# DAC_Output.net
KiCad netlist of a schematic drawn in Altium Designer
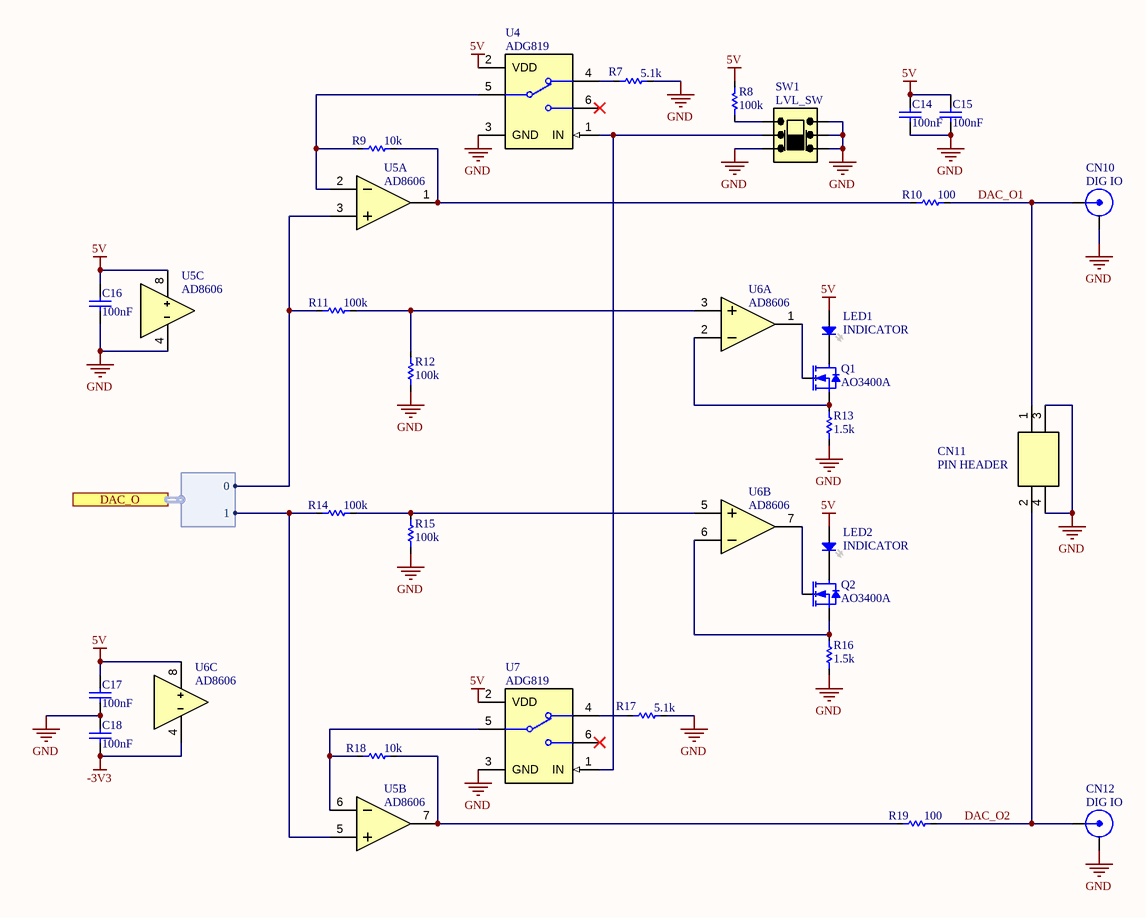
[diagram p0: DAC Output.SchDoc]

(export (version "E")
  (design (tool "Eeschema 10.0.6"))
  (components
    (comp (ref "C14")
      (value "100nF")
      (footprint "CAP_CHIP_0603")
      (description "0603 Multilayer Ceramic Capacitors MLCC")
      (fields (field (name "TOLERANCE") "10%") (field (name "PARTNUMBER") "CC0603KRX7R9BB104"))
      (libsource (lib "Sainsbury Wellcome Centre") (part "Cap"))
    )
    (comp (ref "C15")
      (value "100nF")
      (footprint "CAP_CHIP_0603")
      (description "0603 Multilayer Ceramic Capacitors MLCC")
      (fields (field (name "TOLERANCE") "10%") (field (name "PARTNUMBER") "CC0603KRX7R9BB104"))
      (libsource (lib "Sainsbury Wellcome Centre") (part "Cap"))
    )
    (comp (ref "C16")
      (value "100nF")
      (footprint "CAP_CHIP_0603")
      (description "0603 Multilayer Ceramic Capacitors MLCC")
      (fields (field (name "TOLERANCE") "10%") (field (name "PARTNUMBER") "CC0603KRX7R9BB104"))
      (libsource (lib "Sainsbury Wellcome Centre") (part "Cap"))
    )
    (comp (ref "C17")
      (value "100nF")
      (footprint "CAP_CHIP_0603")
      (description "0603 Multilayer Ceramic Capacitors MLCC")
      (fields (field (name "TOLERANCE") "10%") (field (name "PARTNUMBER") "CC0603KRX7R9BB104"))
      (libsource (lib "Sainsbury Wellcome Centre") (part "Cap"))
    )
    (comp (ref "C18")
      (value "100nF")
      (footprint "CAP_CHIP_0603")
      (description "0603 Multilayer Ceramic Capacitors MLCC")
      (fields (field (name "TOLERANCE") "10%") (field (name "PARTNUMBER") "CC0603KRX7R9BB104"))
      (libsource (lib "Sainsbury Wellcome Centre") (part "Cap"))
    )
    (comp (ref "CN10")
      (value "DIG IO")
      (footprint "BNC-AMP-112515")
      (description "RF BNC Connector, Female, Board Mount, Solder Terminal, Jack")
      (fields (field (name "PARTNUMBER") "112515"))
      (libsource (lib "Sainsbury Wellcome Centre") (part "RF-Jack"))
    )
    (comp (ref "CN11")
      (value "PIN HEADER")
      (footprint "PIN_2.54_2X2P")
      (fields (field (name "PARTNUMBER") "PZ254V-12-4P"))
      (libsource (lib "Sainsbury Wellcome Centre") (part "Header_2X2P"))
    )
    (comp (ref "CN12")
      (value "DIG IO")
      (footprint "BNC-AMP-112515")
      (description "RF BNC Connector, Female, Board Mount, Solder Terminal, Jack")
      (fields (field (name "PARTNUMBER") "112515"))
      (libsource (lib "Sainsbury Wellcome Centre") (part "RF-Jack"))
    )
    (comp (ref "LED1")
      (value "INDICATOR")
      (footprint "LED_CHIP_0805")
      (description "White 0805 Light Emitting Diodes (LED) ROHS")
      (fields (field (name "PARTNUMBER") "KT-0805W"))
      (libsource (lib "Sainsbury Wellcome Centre") (part "LED-WHITE"))
    )
    (comp (ref "LED2")
      (value "INDICATOR")
      (footprint "LED_CHIP_0805")
      (description "White 0805 Light Emitting Diodes (LED) ROHS")
      (fields (field (name "PARTNUMBER") "KT-0805W"))
      (libsource (lib "Sainsbury Wellcome Centre") (part "LED-WHITE"))
    )
    (comp (ref "Q1")
      (value "AO3400A")
      (footprint "SOT23")
      (description "30V 5.7A 26.5mΩ@10V,5.7A 1.4W 1.5V@250uA 1 NChannel SOT-23-3L MOSFETs")
      (fields (field (name "PARTNUMBER") "AO3400A"))
      (libsource (lib "Sainsbury Wellcome Centre") (part "NMOS"))
    )
    (comp (ref "Q2")
      (value "AO3400A")
      (footprint "SOT23")
      (description "30V 5.7A 26.5mΩ@10V,5.7A 1.4W 1.5V@250uA 1 NChannel SOT-23-3L MOSFETs")
      (fields (field (name "PARTNUMBER") "AO3400A"))
      (libsource (lib "Sainsbury Wellcome Centre") (part "NMOS"))
    )
    (comp (ref "R7")
      (value "5.1k")
      (footprint "RES_CHIP_0603")
      (description "100mW Thick Film Resistors 75V ±100ppm/℃ ±1% 0603 Chip Resistor")
      (fields (field (name "TOLERANCE") "1%") (field (name "PARTNUMBER") "0603WAF5101T5E"))
      (libsource (lib "Sainsbury Wellcome Centre") (part "Res"))
    )
    (comp (ref "R8")
      (value "100k")
      (footprint "RES_CHIP_0603")
      (description "100mW Thick Film Resistors 75V ±100ppm/℃ ±1% 0603 Chip Resistor")
      (fields (field (name "PARTNUMBER") "0603WAF1003T5E") (field (name "TOLERANCE") "1%"))
      (libsource (lib "Sainsbury Wellcome Centre") (part "Res"))
    )
    (comp (ref "R9")
      (value "10k")
      (footprint "RES_CHIP_0603")
      (description "100mW Thick Film Resistors 75V ±100ppm/℃ ±1% 0603 Chip Resistor")
      (fields (field (name "PARTNUMBER") "0603WAF1002T5E") (field (name "TOLERANCE") "1%"))
      (libsource (lib "Sainsbury Wellcome Centre") (part "Res"))
    )
    (comp (ref "R10")
      (value "100")
      (footprint "RES_CHIP_0603")
      (description "100mW Thick Film Resistors 75V ±100ppm/℃ ±1% 0603 Chip Resistor")
      (fields (field (name "PARTNUMBER") "0603WAF1000T5E") (field (name "TOLERANCE") "1%"))
      (libsource (lib "Sainsbury Wellcome Centre") (part "Res"))
    )
    (comp (ref "R11")
      (value "100k")
      (footprint "RES_CHIP_0603")
      (description "100mW Thick Film Resistors 75V ±100ppm/℃ ±1% 0603 Chip Resistor")
      (fields (field (name "PARTNUMBER") "0603WAF1003T5E") (field (name "TOLERANCE") "1%"))
      (libsource (lib "Sainsbury Wellcome Centre") (part "Res"))
    )
    (comp (ref "R12")
      (value "100k")
      (footprint "RES_CHIP_0603")
      (description "100mW Thick Film Resistors 75V ±100ppm/℃ ±1% 0603 Chip Resistor")
      (fields (field (name "PARTNUMBER") "0603WAF1003T5E") (field (name "TOLERANCE") "1%"))
      (libsource (lib "Sainsbury Wellcome Centre") (part "Res"))
    )
    (comp (ref "R13")
      (value "1.5k")
      (footprint "RES_CHIP_0603")
      (description "100mW Thick Film Resistors 75V ±100ppm/℃ ±1% 0603 Chip Resistor")
      (fields (field (name "TOLERANCE") "1%") (field (name "PARTNUMBER") "0603WAF1501T5E"))
      (libsource (lib "Sainsbury Wellcome Centre") (part "Res"))
    )
    (comp (ref "R14")
      (value "100k")
      (footprint "RES_CHIP_0603")
      (description "100mW Thick Film Resistors 75V ±100ppm/℃ ±1% 0603 Chip Resistor")
      (fields (field (name "PARTNUMBER") "0603WAF1003T5E") (field (name "TOLERANCE") "1%"))
      (libsource (lib "Sainsbury Wellcome Centre") (part "Res"))
    )
    (comp (ref "R15")
      (value "100k")
      (footprint "RES_CHIP_0603")
      (description "100mW Thick Film Resistors 75V ±100ppm/℃ ±1% 0603 Chip Resistor")
      (fields (field (name "PARTNUMBER") "0603WAF1003T5E") (field (name "TOLERANCE") "1%"))
      (libsource (lib "Sainsbury Wellcome Centre") (part "Res"))
    )
    (comp (ref "R16")
      (value "1.5k")
      (footprint "RES_CHIP_0603")
      (description "100mW Thick Film Resistors 75V ±100ppm/℃ ±1% 0603 Chip Resistor")
      (fields (field (name "TOLERANCE") "1%") (field (name "PARTNUMBER") "0603WAF1501T5E"))
      (libsource (lib "Sainsbury Wellcome Centre") (part "Res"))
    )
    (comp (ref "R17")
      (value "5.1k")
      (footprint "RES_CHIP_0603")
      (description "100mW Thick Film Resistors 75V ±100ppm/℃ ±1% 0603 Chip Resistor")
      (fields (field (name "TOLERANCE") "1%") (field (name "PARTNUMBER") "0603WAF5101T5E"))
      (libsource (lib "Sainsbury Wellcome Centre") (part "Res"))
    )
    (comp (ref "R18")
      (value "10k")
      (footprint "RES_CHIP_0603")
      (description "100mW Thick Film Resistors 75V ±100ppm/℃ ±1% 0603 Chip Resistor")
      (fields (field (name "PARTNUMBER") "0603WAF1002T5E") (field (name "TOLERANCE") "1%"))
      (libsource (lib "Sainsbury Wellcome Centre") (part "Res"))
    )
    (comp (ref "R19")
      (value "100")
      (footprint "RES_CHIP_0603")
      (description "100mW Thick Film Resistors 75V ±100ppm/℃ ±1% 0603 Chip Resistor")
      (fields (field (name "PARTNUMBER") "0603WAF1000T5E") (field (name "TOLERANCE") "1%"))
      (libsource (lib "Sainsbury Wellcome Centre") (part "Res"))
    )
    (comp (ref "SW1")
      (value "LVL_SW")
      (footprint "SW_SLIDE_OS202013MT8")
      (description "Switch Slide ON ON DPDT Top Slide 0.3A 30VDC 10000Cycles PC Pins Thru-Hole Bulk")
      (fields (field (name "PARTNUMBER") "OS202013MT8QN1"))
      (libsource (lib "Sainsbury Wellcome Centre") (part "SLIDE_DPDT"))
    )
    (comp (ref "U4")
      (value "ADG819")
      (footprint "SOT23-6")
      (description "Analog Switch/Analog Multiplexer Single 2: 1 Automotive 6-Pin SOT-23 T/R")
      (fields (field (name "PARTNUMBER") "ADG819BRTZ-REEL7"))
      (libsource (lib "Sainsbury Wellcome Centre") (part "ADG819"))
    )
    (comp (ref "U5")
      (value "AD8606")
      (footprint "VSSOP8_3X3_0.65E")
      (description "Operational Amplifier, 2 Func, 750uV Offset-Max, CMOS, PDSO8")
      (fields (field (name "PARTNUMBER") "AD8606ARMZ-REEL"))
      (libsource (lib "Sainsbury Wellcome Centre") (part "OPAMP 8P"))
    )
    (comp (ref "U6")
      (value "AD8606")
      (footprint "VSSOP8_3X3_0.65E")
      (description "Operational Amplifier, 2 Func, 750uV Offset-Max, CMOS, PDSO8")
      (fields (field (name "PARTNUMBER") "AD8606ARMZ-REEL"))
      (libsource (lib "Sainsbury Wellcome Centre") (part "OPAMP 8P"))
    )
    (comp (ref "U7")
      (value "ADG819")
      (footprint "SOT23-6")
      (description "Analog Switch/Analog Multiplexer Single 2: 1 Automotive 6-Pin SOT-23 T/R")
      (fields (field (name "PARTNUMBER") "ADG819BRTZ-REEL7"))
      (libsource (lib "Sainsbury Wellcome Centre") (part "ADG819"))
    )
  )
  (nets
    (net (code "2") (name "-3V3") (class "Default")
      (node (ref "C18") (pin "1") (pinfunction "1_1") (pintype "passive"))
      (node (ref "U6") (pin "4") (pinfunction "V-_4") (pintype "power_in"))
    )
    (net (code "3") (name "/DAC_O1") (class "Default")
      (node (ref "CN10") (pin "1") (pinfunction "SIG_1") (pintype "passive"))
      (node (ref "CN11") (pin "1") (pinfunction "1_1") (pintype "passive"))
      (node (ref "R10") (pin "2") (pinfunction "2_2") (pintype "passive"))
    )
    (net (code "4") (name "/DAC_O2") (class "Default")
      (node (ref "CN11") (pin "2") (pinfunction "2_2") (pintype "passive"))
      (node (ref "CN12") (pin "1") (pinfunction "SIG_1") (pintype "passive"))
      (node (ref "R19") (pin "2") (pinfunction "2_2") (pintype "passive"))
    )
    (net (code "6") (name "5V") (class "Default")
      (node (ref "C14") (pin "2") (pinfunction "2_2") (pintype "passive"))
      (node (ref "C15") (pin "2") (pinfunction "2_2") (pintype "passive"))
      (node (ref "C16") (pin "2") (pinfunction "2_2") (pintype "passive"))
      (node (ref "C17") (pin "2") (pinfunction "2_2") (pintype "passive"))
      (node (ref "LED1") (pin "2") (pinfunction "A_2") (pintype "passive"))
      (node (ref "LED2") (pin "2") (pinfunction "A_2") (pintype "passive"))
      (node (ref "R8") (pin "2") (pinfunction "2_2") (pintype "passive"))
      (node (ref "U4") (pin "2") (pinfunction "VDD_2") (pintype "power_in"))
      (node (ref "U5") (pin "8") (pinfunction "V+_8") (pintype "power_in"))
      (node (ref "U6") (pin "8") (pinfunction "V+_8") (pintype "power_in"))
      (node (ref "U7") (pin "2") (pinfunction "VDD_2") (pintype "power_in"))
    )
    (net (code "7") (name "GND") (class "Default")
      (node (ref "C14") (pin "1") (pinfunction "1_1") (pintype "passive"))
      (node (ref "C15") (pin "1") (pinfunction "1_1") (pintype "passive"))
      (node (ref "C16") (pin "1") (pinfunction "1_1") (pintype "passive"))
      (node (ref "C17") (pin "1") (pinfunction "1_1") (pintype "passive"))
      (node (ref "C18") (pin "2") (pinfunction "2_2") (pintype "passive"))
      (node (ref "CN10") (pin "2") (pinfunction "GND_2") (pintype "passive"))
      (node (ref "CN11") (pin "3") (pinfunction "3_3") (pintype "passive"))
      (node (ref "CN11") (pin "4") (pinfunction "4_4") (pintype "passive"))
      (node (ref "CN12") (pin "2") (pinfunction "GND_2") (pintype "passive"))
      (node (ref "R12") (pin "1") (pinfunction "1_1") (pintype "passive"))
      (node (ref "R13") (pin "1") (pinfunction "1_1") (pintype "passive"))
      (node (ref "R15") (pin "1") (pinfunction "1_1") (pintype "passive"))
      (node (ref "R16") (pin "1") (pinfunction "1_1") (pintype "passive"))
      (node (ref "R17") (pin "2") (pinfunction "2_2") (pintype "passive"))
      (node (ref "R7") (pin "2") (pinfunction "2_2") (pintype "passive"))
      (node (ref "SW1") (pin "1") (pinfunction "NCA_1") (pintype "passive"))
      (node (ref "SW1") (pin "4") (pinfunction "NCB_4") (pintype "passive"))
      (node (ref "SW1") (pin "5") (pinfunction "COMB_5") (pintype "passive"))
      (node (ref "SW1") (pin "6") (pinfunction "NOB_6") (pintype "passive"))
      (node (ref "U4") (pin "3") (pinfunction "GND_3") (pintype "power_in"))
      (node (ref "U5") (pin "4") (pinfunction "V-_4") (pintype "power_in"))
      (node (ref "U7") (pin "3") (pinfunction "GND_3") (pintype "power_in"))
    )
    (net (code "8") (name "Net-(LED1-K)") (class "Default")
      (node (ref "LED1") (pin "1") (pinfunction "K_1") (pintype "passive"))
      (node (ref "Q1") (pin "3") (pinfunction "D_3") (pintype "passive"))
    )
    (net (code "9") (name "Net-(LED2-K)") (class "Default")
      (node (ref "LED2") (pin "1") (pinfunction "K_1") (pintype "passive"))
      (node (ref "Q2") (pin "3") (pinfunction "D_3") (pintype "passive"))
    )
    (net (code "10") (name "Net-(Q1-G)") (class "Default")
      (node (ref "Q1") (pin "1") (pinfunction "G_1") (pintype "passive"))
      (node (ref "U6") (pin "1") (pinfunction "AOUT_1") (pintype "passive"))
    )
    (net (code "11") (name "Net-(Q1-S)") (class "Default")
      (node (ref "Q1") (pin "2") (pinfunction "S_2") (pintype "passive"))
      (node (ref "R13") (pin "2") (pinfunction "2_2") (pintype "passive"))
      (node (ref "U6") (pin "2") (pinfunction "A-_2") (pintype "passive"))
    )
    (net (code "12") (name "Net-(Q2-G)") (class "Default")
      (node (ref "Q2") (pin "1") (pinfunction "G_1") (pintype "passive"))
      (node (ref "U6") (pin "7") (pinfunction "BOUT_7") (pintype "passive"))
    )
    (net (code "13") (name "Net-(Q2-S)") (class "Default")
      (node (ref "Q2") (pin "2") (pinfunction "S_2") (pintype "passive"))
      (node (ref "R16") (pin "2") (pinfunction "2_2") (pintype "passive"))
      (node (ref "U6") (pin "6") (pinfunction "B-_6") (pintype "passive"))
    )
    (net (code "14") (name "Net-(SW1-COMA)") (class "Default")
      (node (ref "SW1") (pin "2") (pinfunction "COMA_2") (pintype "passive"))
      (node (ref "U4") (pin "1") (pinfunction "IN_1") (pintype "input"))
      (node (ref "U7") (pin "1") (pinfunction "IN_1") (pintype "input"))
    )
    (net (code "15") (name "Net-(SW1-NOA)") (class "Default")
      (node (ref "R8") (pin "1") (pinfunction "1_1") (pintype "passive"))
      (node (ref "SW1") (pin "3") (pinfunction "NOA_3") (pintype "passive"))
    )
    (net (code "16") (name "Net-(U4-D)") (class "Default")
      (node (ref "R9") (pin "1") (pinfunction "1_1") (pintype "passive"))
      (node (ref "U4") (pin "5") (pinfunction "D_5") (pintype "passive"))
      (node (ref "U5") (pin "2") (pinfunction "A-_2") (pintype "passive"))
    )
    (net (code "17") (name "Net-(U4-S1)") (class "Default")
      (node (ref "R7") (pin "1") (pinfunction "1_1") (pintype "passive"))
      (node (ref "U4") (pin "4") (pinfunction "S1_4") (pintype "passive"))
    )
    (net (code "18") (name "Net-(U5A-A+)") (class "Default")
      (node (ref "R11") (pin "2") (pinfunction "2_2") (pintype "passive"))
      (node (ref "U5") (pin "3") (pinfunction "A+_3") (pintype "passive"))
    )
    (net (code "19") (name "Net-(U5A-AOUT)") (class "Default")
      (node (ref "R10") (pin "1") (pinfunction "1_1") (pintype "passive"))
      (node (ref "R9") (pin "2") (pinfunction "2_2") (pintype "passive"))
      (node (ref "U5") (pin "1") (pinfunction "AOUT_1") (pintype "passive"))
    )
    (net (code "20") (name "Net-(U5B-B+)") (class "Default")
      (node (ref "R14") (pin "2") (pinfunction "2_2") (pintype "passive"))
      (node (ref "U5") (pin "5") (pinfunction "B+_5") (pintype "passive"))
    )
    (net (code "21") (name "Net-(U5B-B-)") (class "Default")
      (node (ref "R18") (pin "1") (pinfunction "1_1") (pintype "passive"))
      (node (ref "U5") (pin "6") (pinfunction "B-_6") (pintype "passive"))
      (node (ref "U7") (pin "5") (pinfunction "D_5") (pintype "passive"))
    )
    (net (code "22") (name "Net-(U5B-BOUT)") (class "Default")
      (node (ref "R18") (pin "2") (pinfunction "2_2") (pintype "passive"))
      (node (ref "R19") (pin "1") (pinfunction "1_1") (pintype "passive"))
      (node (ref "U5") (pin "7") (pinfunction "BOUT_7") (pintype "passive"))
    )
    (net (code "23") (name "Net-(U6A-A+)") (class "Default")
      (node (ref "R11") (pin "1") (pinfunction "1_1") (pintype "passive"))
      (node (ref "R12") (pin "2") (pinfunction "2_2") (pintype "passive"))
      (node (ref "U6") (pin "3") (pinfunction "A+_3") (pintype "passive"))
    )
    (net (code "24") (name "Net-(U6B-B+)") (class "Default")
      (node (ref "R14") (pin "1") (pinfunction "1_1") (pintype "passive"))
      (node (ref "R15") (pin "2") (pinfunction "2_2") (pintype "passive"))
      (node (ref "U6") (pin "5") (pinfunction "B+_5") (pintype "passive"))
    )
    (net (code "25") (name "Net-(U7-S1)") (class "Default")
      (node (ref "R17") (pin "1") (pinfunction "1_1") (pintype "passive"))
      (node (ref "U7") (pin "4") (pinfunction "S1_4") (pintype "passive"))
    )
    (net (code "26") (name "unconnected-(U4-S2-Pad6)") (class "Default")
      (node (ref "U4") (pin "6") (pinfunction "S2_6") (pintype "passive+no_connect"))
    )
    (net (code "27") (name "unconnected-(U7-S2-Pad6)") (class "Default")
      (node (ref "U7") (pin "6") (pinfunction "S2_6") (pintype "passive+no_connect"))
    )
  )
)
